# ESP-Gateway.net
KiCad netlist of a schematic drawn in EAGLE
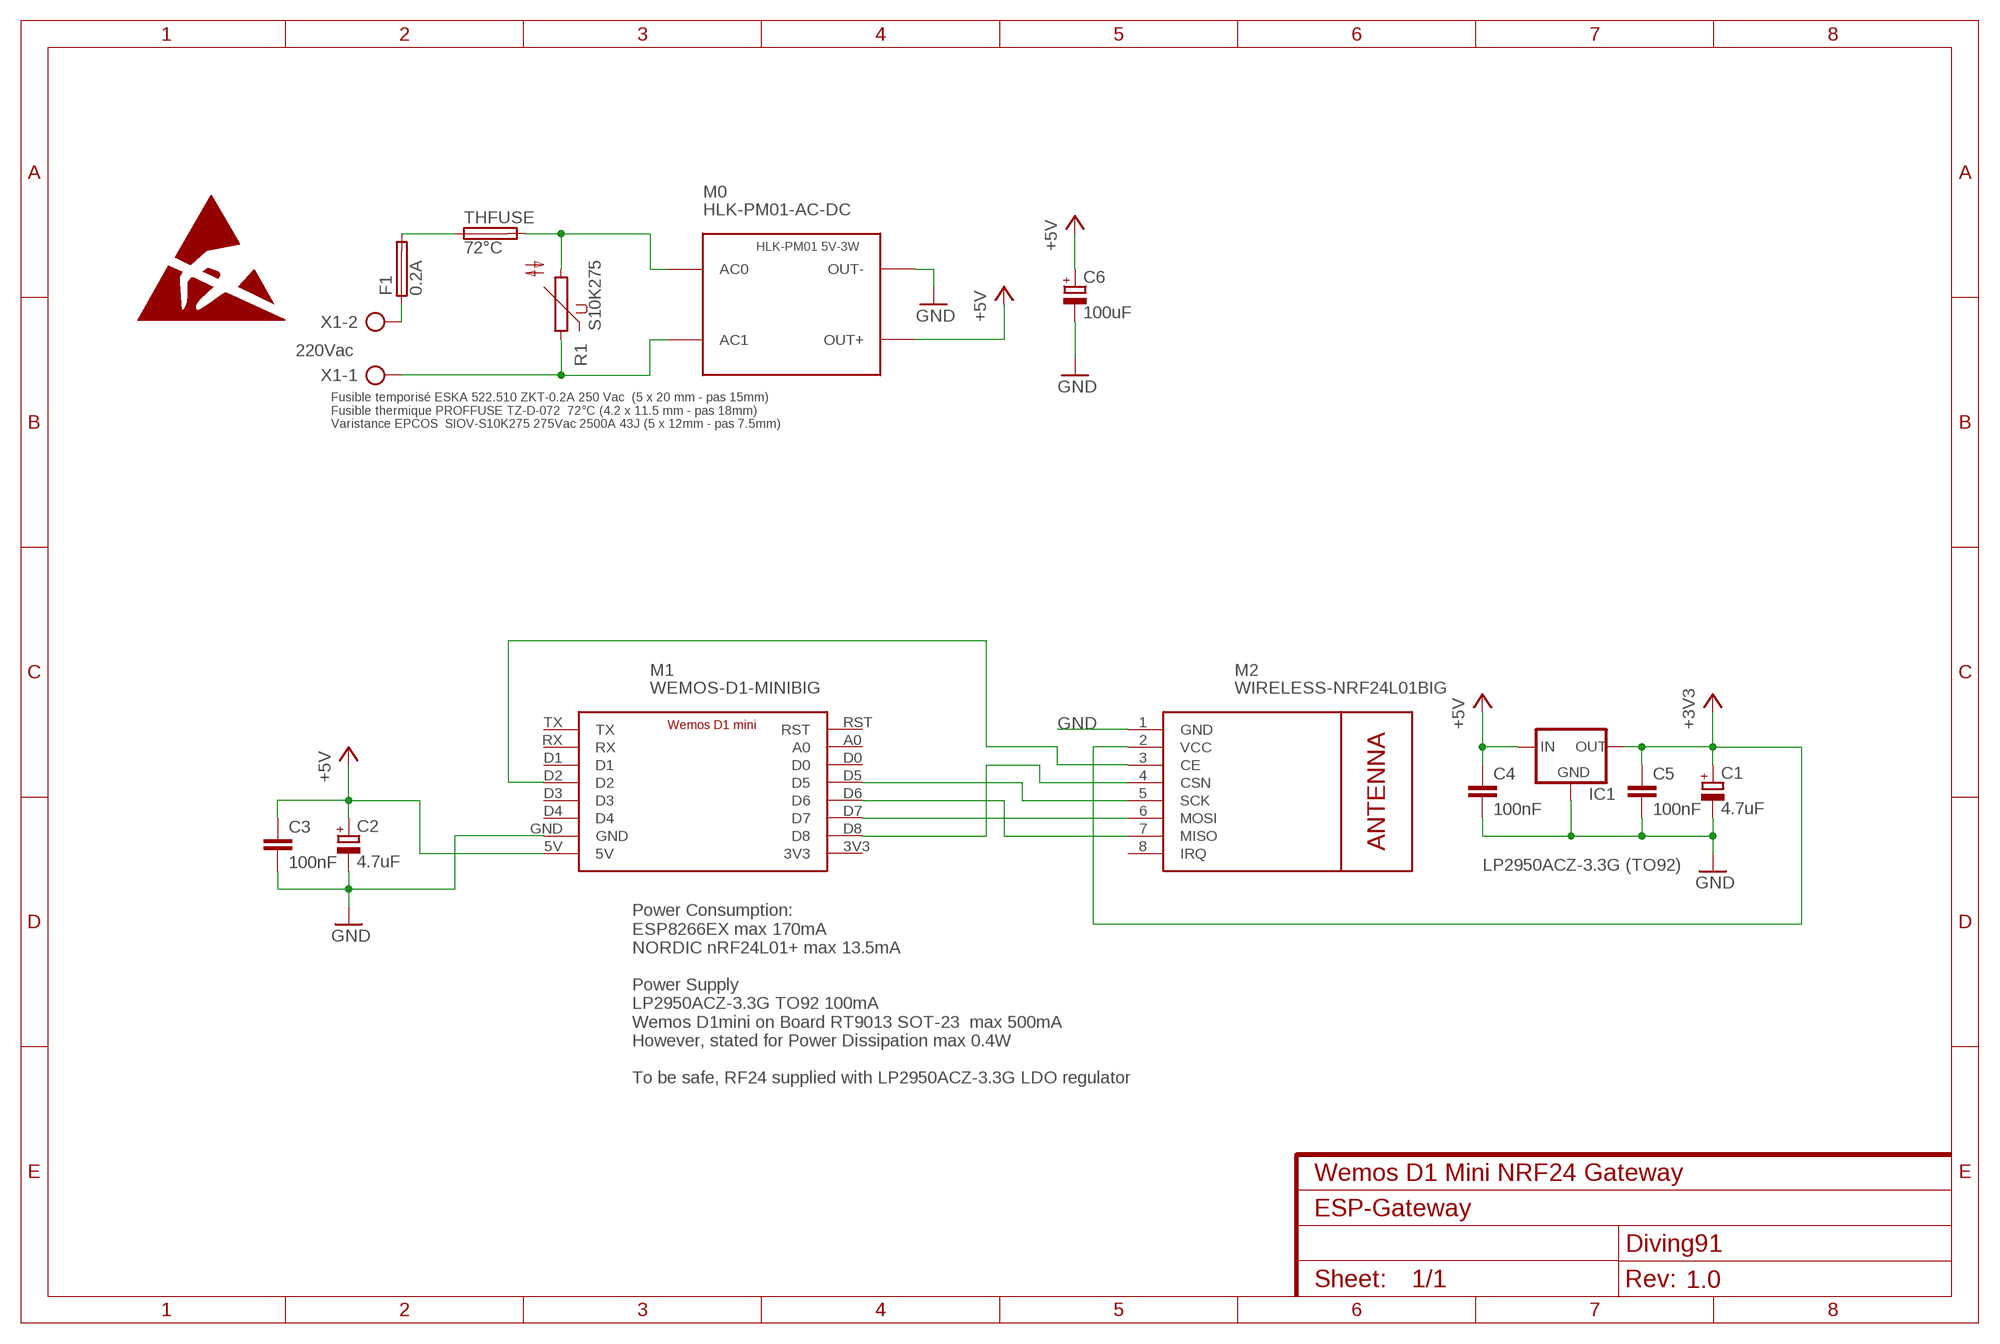
[diagram p0: schematic, sheet 1]

(export (version "E")
  (design (tool "Eeschema 10.0.6"))
  (components
    (comp (ref "C1")
      (value "4.7uF")
      (footprint "eagle-import:E2-5@1")
      (libsource (lib "eagle-import") (part "CPOL-RAD5X12E2-5"))
    )
    (comp (ref "C2")
      (value "4.7uF")
      (footprint "eagle-import:E2-5@1")
      (libsource (lib "eagle-import") (part "CPOL-RAD5X12E2-5"))
    )
    (comp (ref "C3")
      (value "100nF")
      (footprint "eagle-import:C2.5-4")
      (libsource (lib "eagle-import") (part "C3202.5/4"))
    )
    (comp (ref "C4")
      (value "100nF")
      (footprint "eagle-import:C2.5-4")
      (libsource (lib "eagle-import") (part "C3202.5/4"))
    )
    (comp (ref "C5")
      (value "100nF")
      (footprint "eagle-import:C2.5-4")
      (libsource (lib "eagle-import") (part "C3202.5/4"))
    )
    (comp (ref "C6")
      (value "100uF")
      (footprint "eagle-import:E3-8")
      (libsource (lib "eagle-import") (part "CPOL-RADE3-8"))
    )
    (comp (ref "F1")
      (value "0.2A")
      (footprint "eagle-import:PTF75")
      (libsource (lib "eagle-import") (part "PTF75"))
    )
    (comp (ref "IC1")
      (value "LP2950ACZ-3.3G (TO92)")
      (footprint "eagle-import:DC-DC-TO92L")
      (libsource (lib "eagle-import") (part "78LXXTO92L"))
    )
    (comp (ref "M0")
      (value "HLK-PM01-AC-DC")
      (footprint "eagle-import:HLK-PM01-AC-DC")
      (libsource (lib "eagle-import") (part "HLK-PM01-AC-DC"))
    )
    (comp (ref "M1")
      (value "WEMOS-D1-MINIBIG")
      (footprint "eagle-import:WEMOS-D1-MINI-DIY")
      (libsource (lib "eagle-import") (part "WEMOS-D1-MINIBIG"))
    )
    (comp (ref "M2")
      (value "WIRELESS-NRF24L01BIG")
      (footprint "eagle-import:WIRELESS-NRF24L01-DIY")
      (libsource (lib "eagle-import") (part "WIRELESS-NRF24L01BIG"))
    )
    (comp (ref "R1")
      (value "S10K275")
      (footprint "eagle-import:S10K275")
      (libsource (lib "eagle-import") (part "S10K275"))
    )
    (comp (ref "THFUSE")
      (value "72°C")
      (footprint "eagle-import:PROFFUSE-TZ-D")
      (libsource (lib "eagle-import") (part "PROFFUSE-TZ-D"))
    )
    (comp (ref "X1")
      (value "220Vac")
      (footprint "eagle-import:DG301-5.0")
      (libsource (lib "eagle-import") (part "DG301-5.0"))
    )
  )
  (nets
    (net (code "1") (name "+3V3") (class "Default")
      (node (ref "C1") (pin "+") (pinfunction "+_+") (pintype "passive"))
      (node (ref "C5") (pin "1") (pinfunction "1_1") (pintype "passive"))
      (node (ref "IC1") (pin "OUT") (pinfunction "OUT_OUT") (pintype "passive"))
      (node (ref "M2") (pin "2") (pinfunction "VCC_2") (pintype "power_in"))
    )
    (net (code "2") (name "+5V") (class "Default")
      (node (ref "C2") (pin "+") (pinfunction "+_+") (pintype "passive"))
      (node (ref "C3") (pin "1") (pinfunction "1_1") (pintype "passive"))
      (node (ref "C4") (pin "1") (pinfunction "1_1") (pintype "passive"))
      (node (ref "C6") (pin "+") (pinfunction "+_+") (pintype "passive"))
      (node (ref "IC1") (pin "IN") (pinfunction "IN_IN") (pintype "input"))
      (node (ref "M0") (pin "OUT+") (pinfunction "OUT+_OUT+") (pintype "bidirectional"))
      (node (ref "M1") (pin "5V") (pinfunction "5V_5V") (pintype "power_in"))
    )
    (net (code "3") (name "/3V3") (class "Default")
      (node (ref "M1") (pin "3V3") (pinfunction "3V3_3V3") (pintype "power_in"))
    )
    (net (code "4") (name "GND") (class "Default")
      (node (ref "C1") (pin "-") (pinfunction "-_-") (pintype "passive"))
      (node (ref "C2") (pin "-") (pinfunction "-_-") (pintype "passive"))
      (node (ref "C3") (pin "2") (pinfunction "2_2") (pintype "passive"))
      (node (ref "C4") (pin "2") (pinfunction "2_2") (pintype "passive"))
      (node (ref "C5") (pin "2") (pinfunction "2_2") (pintype "passive"))
      (node (ref "C6") (pin "-") (pinfunction "-_-") (pintype "passive"))
      (node (ref "IC1") (pin "GND") (pinfunction "GND_GND") (pintype "input"))
      (node (ref "M0") (pin "OUT-") (pinfunction "OUT-_OUT-") (pintype "bidirectional"))
      (node (ref "M1") (pin "GND") (pinfunction "GND_GND") (pintype "power_in"))
      (node (ref "M2") (pin "1") (pinfunction "GND_1") (pintype "power_in"))
    )
    (net (code "5") (name "Net-(F1-Pad2)") (class "Default")
      (node (ref "F1") (pin "2") (pinfunction "2_2") (pintype "passive"))
      (node (ref "THFUSE") (pin "1") (pinfunction "1_1") (pintype "passive"))
    )
    (net (code "6") (name "Net-(M0-PadAC0)") (class "Default")
      (node (ref "M0") (pin "AC0") (pinfunction "AC0_AC0") (pintype "bidirectional"))
      (node (ref "R1") (pin "2") (pinfunction "2_2") (pintype "passive"))
      (node (ref "THFUSE") (pin "2") (pinfunction "2_2") (pintype "passive"))
    )
    (net (code "7") (name "Net-(M2-CE)") (class "Default")
      (node (ref "M1") (pin "D2") (pinfunction "D2_D2") (pintype "bidirectional"))
      (node (ref "M2") (pin "3") (pinfunction "CE_3") (pintype "bidirectional"))
    )
    (net (code "8") (name "Net-(M2-CSN)") (class "Default")
      (node (ref "M1") (pin "D8") (pinfunction "D8_D8") (pintype "bidirectional"))
      (node (ref "M2") (pin "4") (pinfunction "CSN_4") (pintype "bidirectional"))
    )
    (net (code "9") (name "Net-(M2-MISO)") (class "Default")
      (node (ref "M1") (pin "D6") (pinfunction "D6_D6") (pintype "bidirectional"))
      (node (ref "M2") (pin "7") (pinfunction "MISO_7") (pintype "bidirectional"))
    )
    (net (code "10") (name "Net-(M2-MOSI)") (class "Default")
      (node (ref "M1") (pin "D7") (pinfunction "D7_D7") (pintype "bidirectional"))
      (node (ref "M2") (pin "6") (pinfunction "MOSI_6") (pintype "bidirectional"))
    )
    (net (code "11") (name "Net-(M2-SCK)") (class "Default")
      (node (ref "M1") (pin "D5") (pinfunction "D5_D5") (pintype "bidirectional"))
      (node (ref "M2") (pin "5") (pinfunction "SCK_5") (pintype "bidirectional"))
    )
    (net (code "12") (name "Net-(X1A-KL)") (class "Default")
      (node (ref "M0") (pin "AC1") (pinfunction "AC1_AC1") (pintype "bidirectional"))
      (node (ref "R1") (pin "1") (pinfunction "1_1") (pintype "passive"))
      (node (ref "X1") (pin "1") (pinfunction "KL_1") (pintype "passive"))
    )
    (net (code "13") (name "Net-(X1B-KL)") (class "Default")
      (node (ref "F1") (pin "1") (pinfunction "1_1") (pintype "passive"))
      (node (ref "X1") (pin "2") (pinfunction "KL_2") (pintype "passive"))
    )
    (net (code "14") (name "unconnected-(M1-PadA0)") (class "Default")
      (node (ref "M1") (pin "A0") (pinfunction "A0_A0") (pintype "bidirectional"))
    )
    (net (code "15") (name "unconnected-(M1-PadD0)") (class "Default")
      (node (ref "M1") (pin "D0") (pinfunction "D0_D0") (pintype "bidirectional"))
    )
    (net (code "16") (name "unconnected-(M1-PadD1)") (class "Default")
      (node (ref "M1") (pin "D1") (pinfunction "D1_D1") (pintype "bidirectional"))
    )
    (net (code "17") (name "unconnected-(M1-PadD3)") (class "Default")
      (node (ref "M1") (pin "D3") (pinfunction "D3_D3") (pintype "bidirectional"))
    )
    (net (code "18") (name "unconnected-(M1-PadD4)") (class "Default")
      (node (ref "M1") (pin "D4") (pinfunction "D4_D4") (pintype "bidirectional"))
    )
    (net (code "19") (name "unconnected-(M1-PadRST)") (class "Default")
      (node (ref "M1") (pin "RST") (pinfunction "RST_RST") (pintype "bidirectional"))
    )
    (net (code "20") (name "unconnected-(M1-PadRX)") (class "Default")
      (node (ref "M1") (pin "RX") (pinfunction "RX_RX") (pintype "bidirectional"))
    )
    (net (code "21") (name "unconnected-(M1-PadTX)") (class "Default")
      (node (ref "M1") (pin "TX") (pinfunction "TX_TX") (pintype "bidirectional"))
    )
    (net (code "22") (name "unconnected-(M2-IRQ-Pad8)") (class "Default")
      (node (ref "M2") (pin "8") (pinfunction "IRQ_8") (pintype "bidirectional"))
    )
  )
)
